# Converter_3V3-1V8.net
KiCad netlist of a schematic drawn in Altium Designer
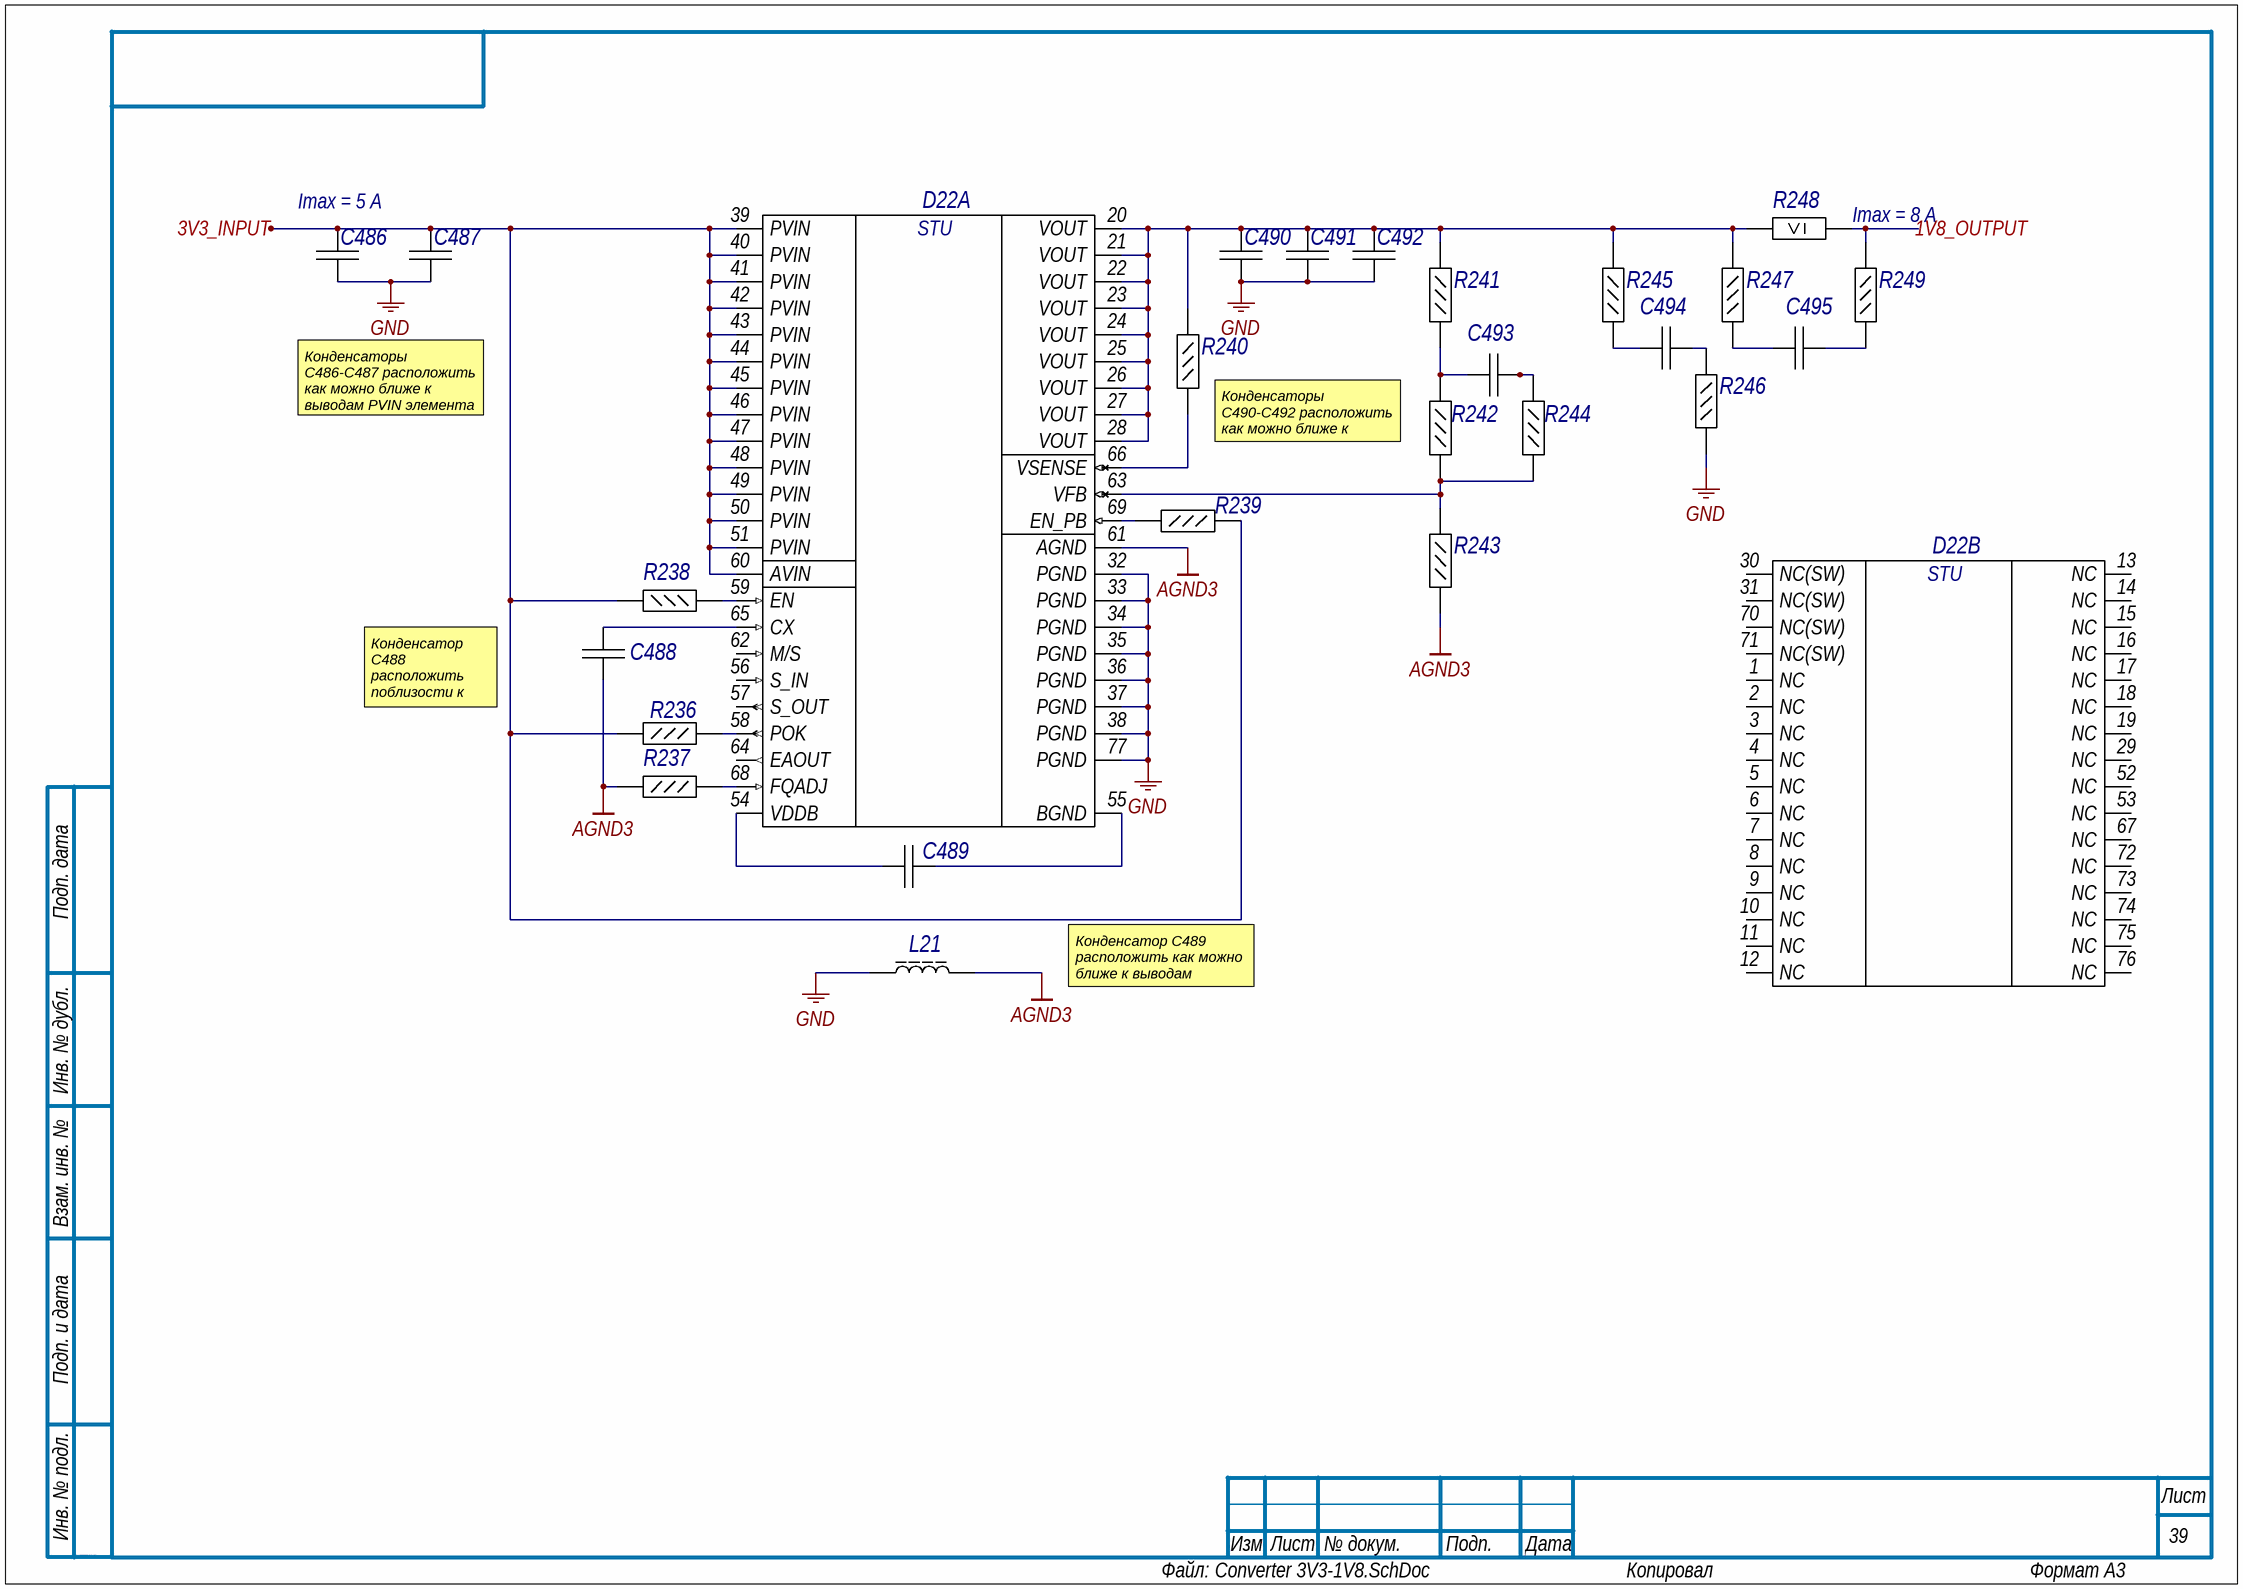
[diagram p0: Converter 3V3-1V8.SchDoc]

(export (version "E")
  (design (tool "Eeschema 10.0.6"))
  (components
    (comp (ref "C486")
      (value "C3216X5R1A476M160AB")
      (footprint "CAPC3216X180X20ML20")
      (description "Chip Capacitor, 47 uF, +/- 20%, 10 V, -55 to 85 degC, 1206 (3216 Metric), RoHS, Tape and Reel")
      (fields (field (name "TOLERANCE") "20%"))
      (libsource (lib "MiniPC DB") (part "CAP_NP"))
    )
    (comp (ref "C487")
      (value "C3216X5R1A476M160AB")
      (footprint "CAPC3216X180X20ML20")
      (description "Chip Capacitor, 47 uF, +/- 20%, 10 V, -55 to 85 degC, 1206 (3216 Metric), RoHS, Tape and Reel")
      (fields (field (name "TOLERANCE") "20%"))
      (libsource (lib "MiniPC DB") (part "CAP_NP"))
    )
    (comp (ref "C488")
      (value "VJ0402Y153JXQPW1BC")
      (footprint "CAPC1005X55X23ML05T8")
      (description "Chip Capacitor, 15 nF, +/- 5%, 10 V, -55 to 125 degC, 0402 (1005 Metric), RoHS, Tape and Reel")
      (fields (field (name "TOLERANCE") "5%"))
      (libsource (lib "MiniPC DB") (part "CAP_NP"))
    )
    (comp (ref "C489")
      (value "GRM155R61A224KE19D")
      (footprint "CAPC1005X55X25NL05T10")
      (description "Chip Capacitor, 220 nF, +/- 10%, 10 V, -55 to 85 degC, 0402 (1005 Metric), RoHS, Tape and Reel")
      (fields (field (name "TOLERANCE") "10%") (field (name "MANUFACTURER") "Basic Passives"))
      (libsource (lib "MiniPC DB") (part "CAP_NP"))
    )
    (comp (ref "C490")
      (value "C3216X5R1A476M160AB")
      (footprint "CAPC3216X180X20ML20")
      (description "Chip Capacitor, 47 uF, +/- 20%, 10 V, -55 to 85 degC, 1206 (3216 Metric), RoHS, Tape and Reel")
      (fields (field (name "TOLERANCE") "20%"))
      (libsource (lib "MiniPC DB") (part "CAP_NP"))
    )
    (comp (ref "C491")
      (value "C3216X5R1A476M160AB")
      (footprint "CAPC3216X180X20ML20")
      (description "Chip Capacitor, 47 uF, +/- 20%, 10 V, -55 to 85 degC, 1206 (3216 Metric), RoHS, Tape and Reel")
      (fields (field (name "TOLERANCE") "20%"))
      (libsource (lib "MiniPC DB") (part "CAP_NP"))
    )
    (comp (ref "C492")
      (value "C3216X5R1A476M160AB")
      (footprint "CAPC3216X180X20ML20")
      (description "Chip Capacitor, 47 uF, +/- 20%, 10 V, -55 to 85 degC, 1206 (3216 Metric), RoHS, Tape and Reel")
      (fields (field (name "TOLERANCE") "20%"))
      (libsource (lib "MiniPC DB") (part "CAP_NP"))
    )
    (comp (ref "C493")
      (value "ECJ-0EC1H270J")
      (footprint "CAPC1005X55X20ML5T10")
      (description "Chip Capacitor, 27 pF, +/- 5%, 50 V, -55 to 125 degC, 0402 (1005 Metric), RoHS, Tape and Reel")
      (fields (field (name "TOLERANCE") "5%"))
      (libsource (lib "MiniPC DB") (part "CAP_NP"))
    )
    (comp (ref "C494")
      (value "GRM155R61A224KE19D")
      (footprint "CAPC1005X55X25NL05T10")
      (description "Chip Capacitor, 220 nF, +/- 10%, 10 V, -55 to 85 degC, 0402 (1005 Metric), RoHS, Tape and Reel")
      (fields (field (name "TOLERANCE") "10%") (field (name "MANUFACTURER") "Basic Passives"))
      (libsource (lib "MiniPC DB") (part "CAP_NP"))
    )
    (comp (ref "C495")
      (value "CGB2A1X5R1E105K033BC")
      (footprint "CAPC1005X33X10LL5")
      (description "Chip Capacitor, 1 uF, +/- 10%, 25 V, -55 to 85 degC, 0402 (1005 Metric), RoHS, Tape and Reel")
      (fields (field (name "TOLERANCE") "10%"))
      (libsource (lib "MiniPC DB") (part "CAP_NP"))
    )
    (comp (ref "D22")
      (value "EN63A0QI")
      (footprint "ALTR-QFN-76_A-305_V")
      (libsource (lib "MiniPC DB") (part "EN63A0QI"))
    )
    (comp (ref "L21")
      (value "742792609")
      (footprint "SMD-0603")
      (description "SMD EMI Suppression Ferrite Bead WE-CBF, Z = 30 Ohm")
      (libsource (lib "MiniPC DB") (part "Choke"))
    )
    (comp (ref "R236")
      (value "ERJ-2RKF1003X")
      (footprint "RESC1005X40X25LL05T05")
      (description "Chip Resistor, 100 KOhm, +/- 1%, 100 mW, -55 to 155 degC, 0402 (1005 Metric), RoHS, Tape and Reel")
      (fields (field (name "TOLERANCE") "1%") (field (name "MANUFACTURER") "Basic Passives"))
      (libsource (lib "") (part "RES-0.05_2"))
    )
    (comp (ref "R237")
      (value "ERJ-2RKF5491X")
      (footprint "RESC1005X40X25LL05T05")
      (description "Chip Resistor, 5.49 KOhm, +/- 1%, 100 mW, -55 to 155 degC, 0402 (1005 Metric), RoHS, Tape and Reel")
      (fields (field (name "TOLERANCE") "1%") (field (name "MANUFACTURER") "Basic Passives"))
      (libsource (lib "") (part "RES-0.05_2"))
    )
    (comp (ref "R238")
      (value "ERJ-2GE0R00X")
      (footprint "RESC1005X40X25LL05T05")
      (description "Chip Resistor, 0 mOhm, +/- 5%, 100 mW, -55 to 155 degC, 0402 (1005 Metric), RoHS, Tape and Reel")
      (fields (field (name "TOLERANCE") "5%") (field (name "MANUFACTURER") "Basic Passives"))
      (libsource (lib "") (part "RES-0.05_3"))
    )
    (comp (ref "R239")
      (value "ERJ-2RKF1002X")
      (footprint "RESC1005X40X25LL05T05")
      (description "Chip Resistor, 10 KOhm, +/- 1%, 100 mW, -55 to 155 degC, 0402 (1005 Metric), RoHS, Tape and Reel")
      (fields (field (name "TOLERANCE") "1%") (field (name "MANUFACTURER") "Basic Passives"))
      (libsource (lib "") (part "RES-0.05_2"))
    )
    (comp (ref "R240")
      (value "ERJ-2GE0R00X")
      (footprint "RESC1005X40X25LL05T05")
      (description "Chip Resistor, 0 mOhm, +/- 5%, 100 mW, -55 to 155 degC, 0402 (1005 Metric), RoHS, Tape and Reel")
      (fields (field (name "TOLERANCE") "5%") (field (name "MANUFACTURER") "Basic Passives"))
      (libsource (lib "") (part "RES-0.05_1"))
    )
    (comp (ref "R241")
      (value "ERJ-2GE0R00X")
      (footprint "RESC1005X40X25LL05T05")
      (description "Chip Resistor, 0 mOhm, +/- 5%, 100 mW, -55 to 155 degC, 0402 (1005 Metric), RoHS, Tape and Reel")
      (fields (field (name "TOLERANCE") "5%") (field (name "MANUFACTURER") "Basic Passives"))
      (libsource (lib "MiniPC DB") (part "RES-0.05"))
    )
    (comp (ref "R242")
      (value "CRCW0402160KFKED")
      (footprint "RESC1005X40X25LL05T05")
      (description "Chip Resistor, 160 KOhm, +/- 1%, 63 mW, -55 to 155 degC, 0402 (1005 Metric), RoHS, Tape and Reel")
      (fields (field (name "TOLERANCE") "1%") (field (name "MANUFACTURER") "Basic Passives"))
      (libsource (lib "MiniPC DB") (part "RES-0.05"))
    )
    (comp (ref "R243")
      (value "ERJ-2RKF8062X")
      (footprint "RESC1005X40X25LL05T05")
      (description "Chip Resistor, 80.6 KOhm, +/- 1%, 100 mW, -55 to 155 degC, 0402 (1005 Metric), RoHS, Tape and Reel")
      (fields (field (name "TOLERANCE") "1%") (field (name "MANUFACTURER") "Basic Passives"))
      (libsource (lib "MiniPC DB") (part "RES-0.05"))
    )
    (comp (ref "R244")
      (value "ERJ-2RKF1502X")
      (footprint "RESC1005X40X25LL05T05")
      (description "Chip Resistor, 15 KOhm, +/- 1%, 100 mW, -55 to 155 degC, 0402 (1005 Metric), RoHS, Tape and Reel")
      (fields (field (name "TOLERANCE") "1%") (field (name "MANUFACTURER") "Basic Passives"))
      (libsource (lib "MiniPC DB") (part "RES-0.05"))
    )
    (comp (ref "R245")
      (value "ERJ-2RKF1000X")
      (footprint "RESC1005X40X25LL05T05")
      (description "Chip Resistor, 100 Ohm, +/- 1%, 100 mW, -55 to 155 degC, 0402 (1005 Metric), RoHS, Tape and Reel")
      (fields (field (name "TOLERANCE") "1%") (field (name "MANUFACTURER") "Basic Passives"))
      (libsource (lib "MiniPC DB") (part "RES-0.05"))
    )
    (comp (ref "R246")
      (value "ERJ-2RKF1000X")
      (footprint "RESC1005X40X25LL05T05")
      (description "Chip Resistor, 100 Ohm, +/- 1%, 100 mW, -55 to 155 degC, 0402 (1005 Metric), RoHS, Tape and Reel")
      (fields (field (name "TOLERANCE") "1%") (field (name "MANUFACTURER") "Basic Passives"))
      (libsource (lib "") (part "RES-0.05_1"))
    )
    (comp (ref "R247")
      (value "ERJ-2RKF1002X")
      (footprint "RESC1005X40X25LL05T05")
      (description "Chip Resistor, 10 KOhm, +/- 1%, 100 mW, -55 to 155 degC, 0402 (1005 Metric), RoHS, Tape and Reel")
      (fields (field (name "TOLERANCE") "1%") (field (name "MANUFACTURER") "Basic Passives"))
      (libsource (lib "") (part "RES-0.05_1"))
    )
    (comp (ref "R248")
      (value "CSS2725FTL250")
      (footprint "STAC-CSS2725-099H_V")
      (description "Chip Resistor, 0.25 mOhm, +/- 1%, 4 W, -55 to 225 degC, 2725 (6865 Metric), RoHS, Tape and Reel")
      (fields (field (name "TOLERANCE") "1%"))
      (libsource (lib "MiniPC DB") (part "RES-4"))
    )
    (comp (ref "R249")
      (value "ERJ-2RKF1002X")
      (footprint "RESC1005X40X25LL05T05")
      (description "Chip Resistor, 10 KOhm, +/- 1%, 100 mW, -55 to 155 degC, 0402 (1005 Metric), RoHS, Tape and Reel")
      (fields (field (name "TOLERANCE") "1%") (field (name "MANUFACTURER") "Basic Passives"))
      (libsource (lib "") (part "RES-0.05_1"))
    )
  )
  (nets
    (net (code "1") (name "/1V8_OUTPUT") (class "Default")
      (node (ref "R248") (pin "1") (pinfunction "1_1") (pintype "passive"))
      (node (ref "R249") (pin "2") (pinfunction "2_2") (pintype "passive"))
    )
    (net (code "2") (name "/3V3_INPUT") (class "Default")
      (node (ref "C486") (pin "2") (pinfunction "2_2") (pintype "passive"))
      (node (ref "C487") (pin "2") (pinfunction "2_2") (pintype "passive"))
      (node (ref "D22") (pin "39") (pinfunction "PVIN_39") (pintype "power_in"))
      (node (ref "D22") (pin "40") (pinfunction "PVIN_40") (pintype "power_in"))
      (node (ref "D22") (pin "41") (pinfunction "PVIN_41") (pintype "power_in"))
      (node (ref "D22") (pin "42") (pinfunction "PVIN_42") (pintype "power_in"))
      (node (ref "D22") (pin "43") (pinfunction "PVIN_43") (pintype "power_in"))
      (node (ref "D22") (pin "44") (pinfunction "PVIN_44") (pintype "power_in"))
      (node (ref "D22") (pin "45") (pinfunction "PVIN_45") (pintype "power_in"))
      (node (ref "D22") (pin "46") (pinfunction "PVIN_46") (pintype "power_in"))
      (node (ref "D22") (pin "47") (pinfunction "PVIN_47") (pintype "power_in"))
      (node (ref "D22") (pin "48") (pinfunction "PVIN_48") (pintype "power_in"))
      (node (ref "D22") (pin "49") (pinfunction "PVIN_49") (pintype "power_in"))
      (node (ref "D22") (pin "50") (pinfunction "PVIN_50") (pintype "power_in"))
      (node (ref "D22") (pin "51") (pinfunction "PVIN_51") (pintype "power_in"))
      (node (ref "D22") (pin "60") (pinfunction "AVIN_60") (pintype "power_in"))
      (node (ref "R236") (pin "2") (pinfunction "2_2") (pintype "passive"))
      (node (ref "R238") (pin "1") (pinfunction "1_1") (pintype "passive"))
      (node (ref "R239") (pin "1") (pinfunction "1_1") (pintype "passive"))
    )
    (net (code "3") (name "AGND3") (class "Default")
      (node (ref "C488") (pin "1") (pinfunction "1_1") (pintype "passive"))
      (node (ref "D22") (pin "61") (pinfunction "AGND_61") (pintype "power_in"))
      (node (ref "L21") (pin "2") (pinfunction "2_2") (pintype "passive"))
      (node (ref "R237") (pin "2") (pinfunction "2_2") (pintype "passive"))
      (node (ref "R243") (pin "2") (pinfunction "2_2") (pintype "passive"))
    )
    (net (code "4") (name "GND") (class "Default")
      (node (ref "C486") (pin "1") (pinfunction "1_1") (pintype "passive"))
      (node (ref "C487") (pin "1") (pinfunction "1_1") (pintype "passive"))
      (node (ref "C490") (pin "1") (pinfunction "1_1") (pintype "passive"))
      (node (ref "C491") (pin "1") (pinfunction "1_1") (pintype "passive"))
      (node (ref "C492") (pin "1") (pinfunction "1_1") (pintype "passive"))
      (node (ref "D22") (pin "32") (pinfunction "PGND_32") (pintype "power_in"))
      (node (ref "D22") (pin "33") (pinfunction "PGND_33") (pintype "power_in"))
      (node (ref "D22") (pin "34") (pinfunction "PGND_34") (pintype "power_in"))
      (node (ref "D22") (pin "35") (pinfunction "PGND_35") (pintype "power_in"))
      (node (ref "D22") (pin "36") (pinfunction "PGND_36") (pintype "power_in"))
      (node (ref "D22") (pin "37") (pinfunction "PGND_37") (pintype "power_in"))
      (node (ref "D22") (pin "38") (pinfunction "PGND_38") (pintype "power_in"))
      (node (ref "D22") (pin "77") (pinfunction "PGND_77") (pintype "power_in"))
      (node (ref "L21") (pin "1") (pinfunction "1_1") (pintype "passive"))
      (node (ref "R246") (pin "1") (pinfunction "1_1") (pintype "passive"))
    )
    (net (code "5") (name "Net-(C490-Pad2)") (class "Default")
      (node (ref "C490") (pin "2") (pinfunction "2_2") (pintype "passive"))
      (node (ref "C491") (pin "2") (pinfunction "2_2") (pintype "passive"))
      (node (ref "C492") (pin "2") (pinfunction "2_2") (pintype "passive"))
      (node (ref "D22") (pin "20") (pinfunction "VOUT_20") (pintype "power_in"))
      (node (ref "D22") (pin "21") (pinfunction "VOUT_21") (pintype "power_in"))
      (node (ref "D22") (pin "22") (pinfunction "VOUT_22") (pintype "power_in"))
      (node (ref "D22") (pin "23") (pinfunction "VOUT_23") (pintype "power_in"))
      (node (ref "D22") (pin "24") (pinfunction "VOUT_24") (pintype "power_in"))
      (node (ref "D22") (pin "25") (pinfunction "VOUT_25") (pintype "power_in"))
      (node (ref "D22") (pin "26") (pinfunction "VOUT_26") (pintype "power_in"))
      (node (ref "D22") (pin "27") (pinfunction "VOUT_27") (pintype "power_in"))
      (node (ref "D22") (pin "28") (pinfunction "VOUT_28") (pintype "power_in"))
      (node (ref "R240") (pin "2") (pinfunction "2_2") (pintype "passive"))
      (node (ref "R241") (pin "1") (pinfunction "1_1") (pintype "passive"))
      (node (ref "R245") (pin "1") (pinfunction "1_1") (pintype "passive"))
      (node (ref "R247") (pin "2") (pinfunction "2_2") (pintype "passive"))
      (node (ref "R248") (pin "2") (pinfunction "2_2") (pintype "passive"))
    )
    (net (code "6") (name "Net-(C493-Pad1)") (class "Default")
      (node (ref "C493") (pin "1") (pinfunction "1_1") (pintype "passive"))
      (node (ref "R241") (pin "2") (pinfunction "2_2") (pintype "passive"))
      (node (ref "R242") (pin "1") (pinfunction "1_1") (pintype "passive"))
    )
    (net (code "7") (name "Net-(C493-Pad2)") (class "Default")
      (node (ref "C493") (pin "2") (pinfunction "2_2") (pintype "passive"))
      (node (ref "R244") (pin "1") (pinfunction "1_1") (pintype "passive"))
    )
    (net (code "8") (name "Net-(C494-Pad1)") (class "Default")
      (node (ref "C494") (pin "1") (pinfunction "1_1") (pintype "passive"))
      (node (ref "R245") (pin "2") (pinfunction "2_2") (pintype "passive"))
    )
    (net (code "9") (name "Net-(C494-Pad2)") (class "Default")
      (node (ref "C494") (pin "2") (pinfunction "2_2") (pintype "passive"))
      (node (ref "R246") (pin "2") (pinfunction "2_2") (pintype "passive"))
    )
    (net (code "10") (name "Net-(C495-Pad1)") (class "Default")
      (node (ref "C495") (pin "1") (pinfunction "1_1") (pintype "passive"))
      (node (ref "R247") (pin "1") (pinfunction "1_1") (pintype "passive"))
    )
    (net (code "11") (name "Net-(C495-Pad2)") (class "Default")
      (node (ref "C495") (pin "2") (pinfunction "2_2") (pintype "passive"))
      (node (ref "R249") (pin "1") (pinfunction "1_1") (pintype "passive"))
    )
    (net (code "12") (name "Net-(D22A-BGND)") (class "Default")
      (node (ref "C489") (pin "1") (pinfunction "1_1") (pintype "passive"))
      (node (ref "D22") (pin "55") (pinfunction "BGND_55") (pintype "power_in"))
    )
    (net (code "13") (name "Net-(D22A-CX)") (class "Default")
      (node (ref "C488") (pin "2") (pinfunction "2_2") (pintype "passive"))
      (node (ref "D22") (pin "65") (pinfunction "CX_65") (pintype "input"))
    )
    (net (code "14") (name "Net-(D22A-EN)") (class "Default")
      (node (ref "D22") (pin "59") (pinfunction "EN_59") (pintype "input"))
      (node (ref "R238") (pin "2") (pinfunction "2_2") (pintype "passive"))
    )
    (net (code "15") (name "Net-(D22A-EN_PB)") (class "Default")
      (node (ref "D22") (pin "69") (pinfunction "EN_PB_69") (pintype "input"))
      (node (ref "R239") (pin "2") (pinfunction "2_2") (pintype "passive"))
    )
    (net (code "16") (name "Net-(D22A-FQADJ)") (class "Default")
      (node (ref "D22") (pin "68") (pinfunction "FQADJ_68") (pintype "input"))
      (node (ref "R237") (pin "1") (pinfunction "1_1") (pintype "passive"))
    )
    (net (code "17") (name "Net-(D22A-POK)") (class "Default")
      (node (ref "D22") (pin "58") (pinfunction "POK_58") (pintype "output"))
      (node (ref "R236") (pin "1") (pinfunction "1_1") (pintype "passive"))
    )
    (net (code "18") (name "Net-(D22A-VDDB)") (class "Default")
      (node (ref "C489") (pin "2") (pinfunction "2_2") (pintype "passive"))
      (node (ref "D22") (pin "54") (pinfunction "VDDB_54") (pintype "power_in"))
    )
    (net (code "19") (name "Net-(D22A-VFB)") (class "Default")
      (node (ref "D22") (pin "63") (pinfunction "VFB_63") (pintype "input"))
      (node (ref "R242") (pin "2") (pinfunction "2_2") (pintype "passive"))
      (node (ref "R243") (pin "1") (pinfunction "1_1") (pintype "passive"))
      (node (ref "R244") (pin "2") (pinfunction "2_2") (pintype "passive"))
    )
    (net (code "20") (name "Net-(D22A-VSENSE)") (class "Default")
      (node (ref "D22") (pin "66") (pinfunction "VSENSE_66") (pintype "input"))
      (node (ref "R240") (pin "1") (pinfunction "1_1") (pintype "passive"))
    )
    (net (code "21") (name "unconnected-(D22A-EAOUT-Pad64)") (class "Default")
      (node (ref "D22") (pin "64") (pinfunction "EAOUT_64") (pintype "output"))
    )
    (net (code "22") (name "unconnected-(D22A-M{slash}S-Pad62)") (class "Default")
      (node (ref "D22") (pin "62") (pinfunction "M/S_62") (pintype "input"))
    )
    (net (code "23") (name "unconnected-(D22A-S_IN-Pad56)") (class "Default")
      (node (ref "D22") (pin "56") (pinfunction "S_IN_56") (pintype "input"))
    )
    (net (code "24") (name "unconnected-(D22A-S_OUT-Pad57)") (class "Default")
      (node (ref "D22") (pin "57") (pinfunction "S_OUT_57") (pintype "output"))
    )
    (net (code "25") (name "unconnected-(D22B-NC(SW)-Pad30)") (class "Default")
      (node (ref "D22") (pin "30") (pinfunction "NC(SW)_30") (pintype "passive"))
    )
    (net (code "26") (name "unconnected-(D22B-NC(SW)-Pad31)") (class "Default")
      (node (ref "D22") (pin "31") (pinfunction "NC(SW)_31") (pintype "passive"))
    )
    (net (code "27") (name "unconnected-(D22B-NC(SW)-Pad70)") (class "Default")
      (node (ref "D22") (pin "70") (pinfunction "NC(SW)_70") (pintype "passive"))
    )
    (net (code "28") (name "unconnected-(D22B-NC(SW)-Pad71)") (class "Default")
      (node (ref "D22") (pin "71") (pinfunction "NC(SW)_71") (pintype "passive"))
    )
    (net (code "29") (name "unconnected-(D22B-NC-Pad1)") (class "Default")
      (node (ref "D22") (pin "1") (pinfunction "NC_1") (pintype "passive"))
    )
    (net (code "30") (name "unconnected-(D22B-NC-Pad2)") (class "Default")
      (node (ref "D22") (pin "2") (pinfunction "NC_2") (pintype "passive"))
    )
    (net (code "31") (name "unconnected-(D22B-NC-Pad3)") (class "Default")
      (node (ref "D22") (pin "3") (pinfunction "NC_3") (pintype "passive"))
    )
    (net (code "32") (name "unconnected-(D22B-NC-Pad4)") (class "Default")
      (node (ref "D22") (pin "4") (pinfunction "NC_4") (pintype "passive"))
    )
    (net (code "33") (name "unconnected-(D22B-NC-Pad5)") (class "Default")
      (node (ref "D22") (pin "5") (pinfunction "NC_5") (pintype "passive"))
    )
    (net (code "34") (name "unconnected-(D22B-NC-Pad6)") (class "Default")
      (node (ref "D22") (pin "6") (pinfunction "NC_6") (pintype "passive"))
    )
    (net (code "35") (name "unconnected-(D22B-NC-Pad7)") (class "Default")
      (node (ref "D22") (pin "7") (pinfunction "NC_7") (pintype "passive"))
    )
    (net (code "36") (name "unconnected-(D22B-NC-Pad8)") (class "Default")
      (node (ref "D22") (pin "8") (pinfunction "NC_8") (pintype "passive"))
    )
    (net (code "37") (name "unconnected-(D22B-NC-Pad9)") (class "Default")
      (node (ref "D22") (pin "9") (pinfunction "NC_9") (pintype "passive"))
    )
    (net (code "38") (name "unconnected-(D22B-NC-Pad10)") (class "Default")
      (node (ref "D22") (pin "10") (pinfunction "NC_10") (pintype "passive"))
    )
    (net (code "39") (name "unconnected-(D22B-NC-Pad11)") (class "Default")
      (node (ref "D22") (pin "11") (pinfunction "NC_11") (pintype "passive"))
    )
    (net (code "40") (name "unconnected-(D22B-NC-Pad12)") (class "Default")
      (node (ref "D22") (pin "12") (pinfunction "NC_12") (pintype "passive"))
    )
    (net (code "41") (name "unconnected-(D22B-NC-Pad13)") (class "Default")
      (node (ref "D22") (pin "13") (pinfunction "NC_13") (pintype "passive"))
    )
    (net (code "42") (name "unconnected-(D22B-NC-Pad14)") (class "Default")
      (node (ref "D22") (pin "14") (pinfunction "NC_14") (pintype "passive"))
    )
    (net (code "43") (name "unconnected-(D22B-NC-Pad15)") (class "Default")
      (node (ref "D22") (pin "15") (pinfunction "NC_15") (pintype "passive"))
    )
    (net (code "44") (name "unconnected-(D22B-NC-Pad16)") (class "Default")
      (node (ref "D22") (pin "16") (pinfunction "NC_16") (pintype "passive"))
    )
    (net (code "45") (name "unconnected-(D22B-NC-Pad17)") (class "Default")
      (node (ref "D22") (pin "17") (pinfunction "NC_17") (pintype "passive"))
    )
    (net (code "46") (name "unconnected-(D22B-NC-Pad18)") (class "Default")
      (node (ref "D22") (pin "18") (pinfunction "NC_18") (pintype "passive"))
    )
    (net (code "47") (name "unconnected-(D22B-NC-Pad19)") (class "Default")
      (node (ref "D22") (pin "19") (pinfunction "NC_19") (pintype "passive"))
    )
    (net (code "48") (name "unconnected-(D22B-NC-Pad29)") (class "Default")
      (node (ref "D22") (pin "29") (pinfunction "NC_29") (pintype "passive"))
    )
    (net (code "49") (name "unconnected-(D22B-NC-Pad52)") (class "Default")
      (node (ref "D22") (pin "52") (pinfunction "NC_52") (pintype "passive"))
    )
    (net (code "50") (name "unconnected-(D22B-NC-Pad53)") (class "Default")
      (node (ref "D22") (pin "53") (pinfunction "NC_53") (pintype "passive"))
    )
    (net (code "51") (name "unconnected-(D22B-NC-Pad67)") (class "Default")
      (node (ref "D22") (pin "67") (pinfunction "NC_67") (pintype "passive"))
    )
    (net (code "52") (name "unconnected-(D22B-NC-Pad72)") (class "Default")
      (node (ref "D22") (pin "72") (pinfunction "NC_72") (pintype "passive"))
    )
    (net (code "53") (name "unconnected-(D22B-NC-Pad73)") (class "Default")
      (node (ref "D22") (pin "73") (pinfunction "NC_73") (pintype "passive"))
    )
    (net (code "54") (name "unconnected-(D22B-NC-Pad74)") (class "Default")
      (node (ref "D22") (pin "74") (pinfunction "NC_74") (pintype "passive"))
    )
    (net (code "55") (name "unconnected-(D22B-NC-Pad75)") (class "Default")
      (node (ref "D22") (pin "75") (pinfunction "NC_75") (pintype "passive"))
    )
    (net (code "56") (name "unconnected-(D22B-NC-Pad76)") (class "Default")
      (node (ref "D22") (pin "76") (pinfunction "NC_76") (pintype "passive"))
    )
  )
)
